# 130805_AriloRX_0_0.net
KiCad netlist of a schematic drawn in EAGLE
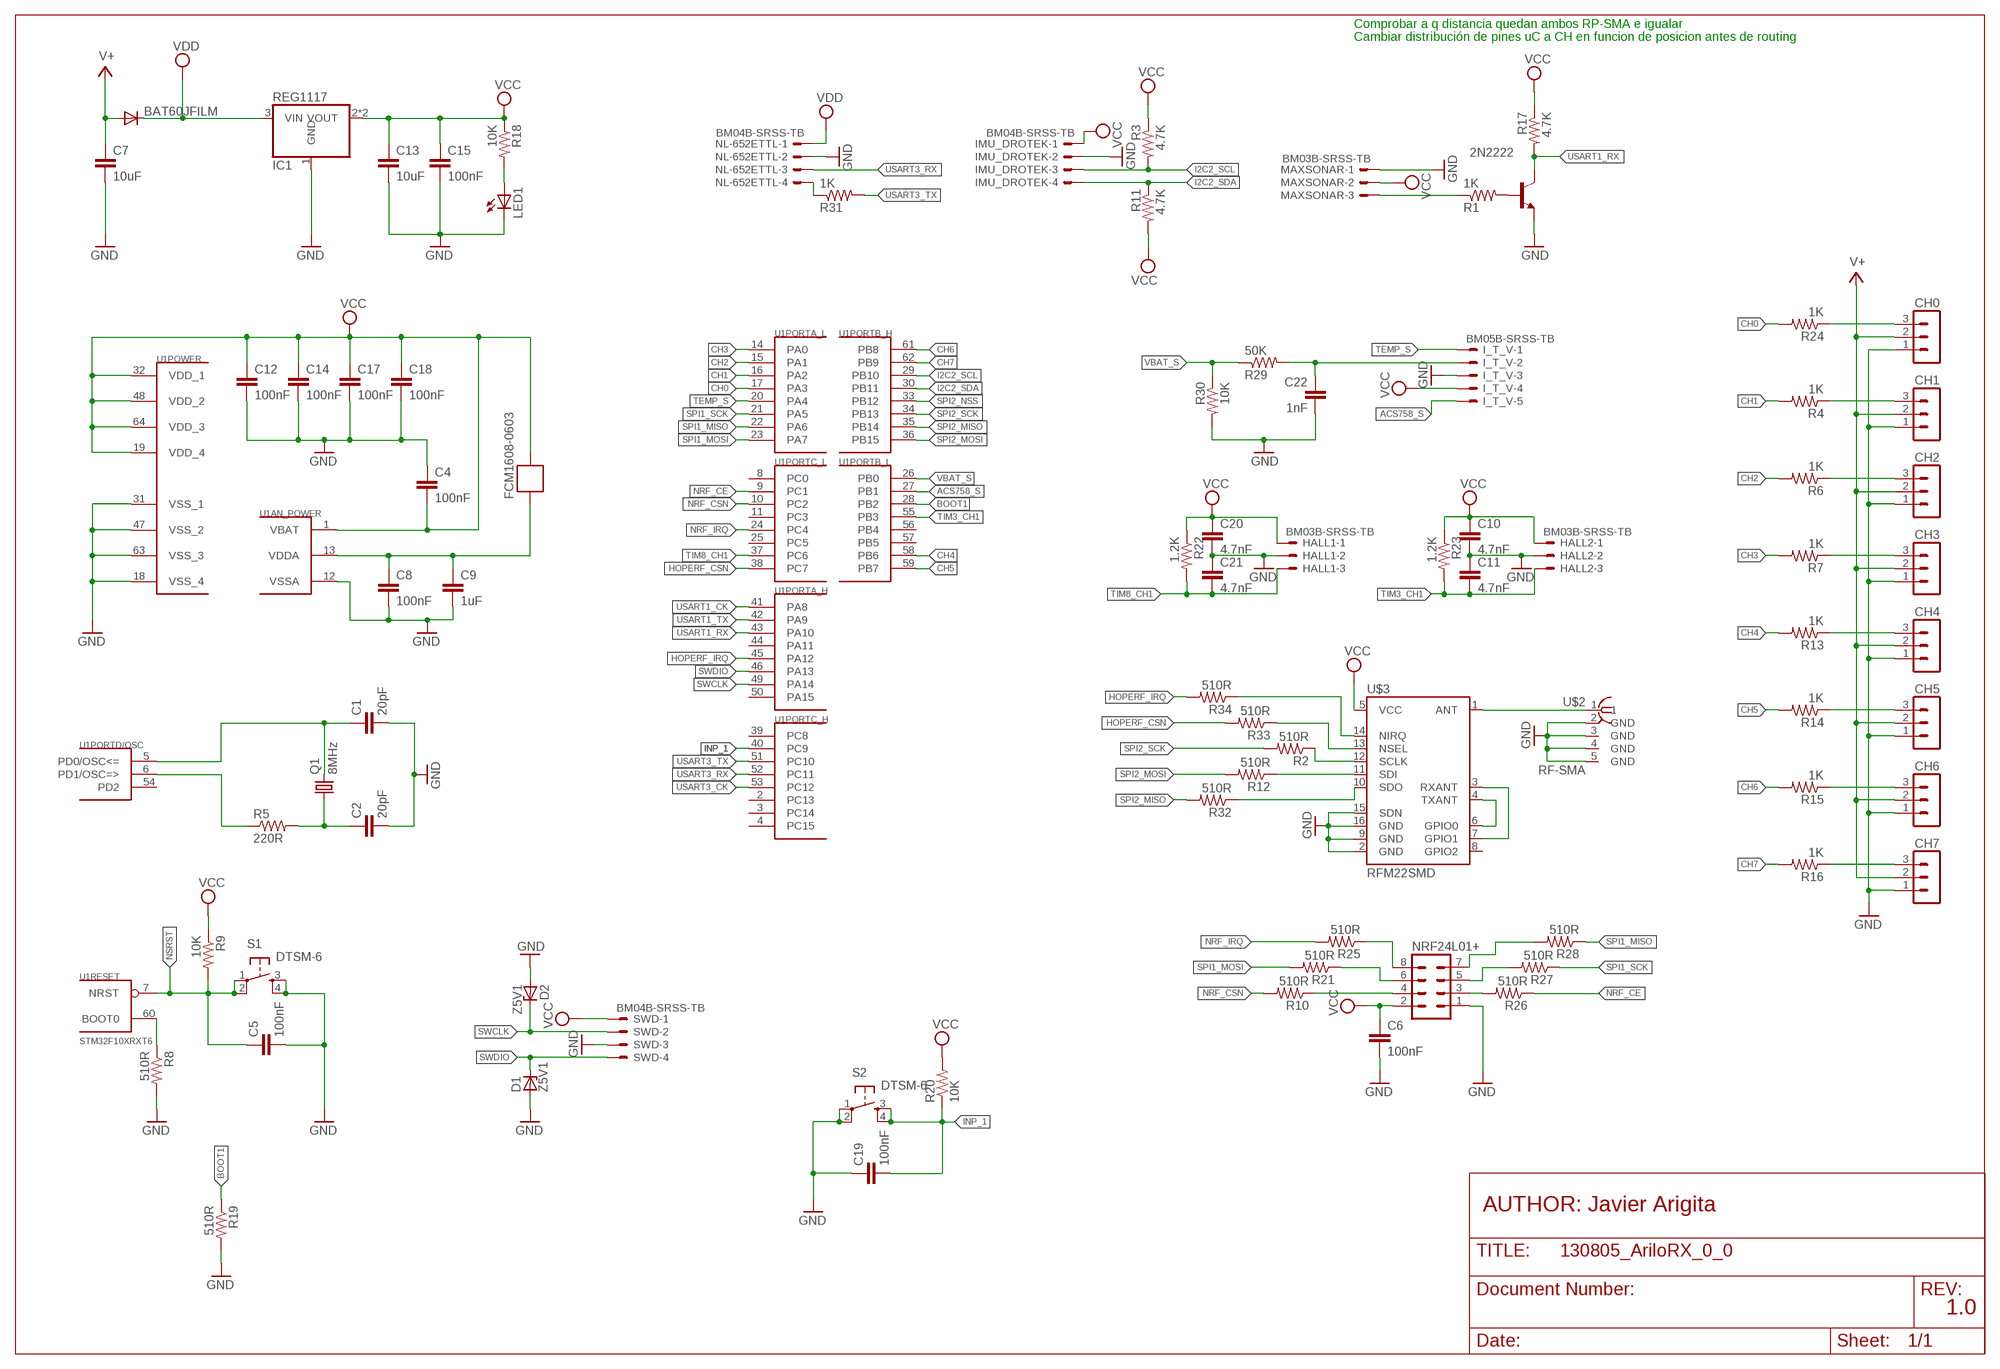
[diagram p0: schematic, sheet 1]

(export (version "E")
  (design (tool "Eeschema 10.0.6"))
  (components
    (comp (ref "2N2222")
      (value "MMBT2222ALT1-NPN-SOT23-BEC")
      (footprint "eagle-import:SOT23-BEC")
      (libsource (lib "eagle-import") (part "-NPN-SOT23-BECMMBT2222ALT1"))
    )
    (comp (ref "BAT60JFILM")
      (value "DIODE-SOD323-R")
      (footprint "eagle-import:SOD323-R")
      (libsource (lib "eagle-import") (part "DIODE-SOD323-R"))
    )
    (comp (ref "C1")
      (value "20pF")
      (footprint "eagle-import:C0805")
      (libsource (lib "eagle-import") (part "C-EUC0805"))
    )
    (comp (ref "C2")
      (value "20pF")
      (footprint "eagle-import:C0805")
      (libsource (lib "eagle-import") (part "C-EUC0805"))
    )
    (comp (ref "C4")
      (value "100nF")
      (footprint "eagle-import:C0805")
      (libsource (lib "eagle-import") (part "C-EUC0805"))
    )
    (comp (ref "C5")
      (value "100nF")
      (footprint "eagle-import:C0805")
      (libsource (lib "eagle-import") (part "C-EUC0805"))
    )
    (comp (ref "C6")
      (value "100nF")
      (footprint "eagle-import:C0805")
      (libsource (lib "eagle-import") (part "C-EUC0805"))
    )
    (comp (ref "C7")
      (value "10uF")
      (footprint "eagle-import:C3216")
      (libsource (lib "eagle-import") (part "resistor_C-EUC3216"))
    )
    (comp (ref "C8")
      (value "100nF")
      (footprint "eagle-import:C0805")
      (libsource (lib "eagle-import") (part "C-EUC0805"))
    )
    (comp (ref "C9")
      (value "1uF")
      (footprint "eagle-import:C3216")
      (libsource (lib "eagle-import") (part "resistor_C-EUC3216"))
    )
    (comp (ref "C10")
      (value "4.7nF")
      (footprint "eagle-import:C0805")
      (libsource (lib "eagle-import") (part "C-EUC0805"))
    )
    (comp (ref "C11")
      (value "4.7nF")
      (footprint "eagle-import:C0805")
      (libsource (lib "eagle-import") (part "C-EUC0805"))
    )
    (comp (ref "C12")
      (value "100nF")
      (footprint "eagle-import:C0805")
      (libsource (lib "eagle-import") (part "C-EUC0805"))
    )
    (comp (ref "C13")
      (value "10uF")
      (footprint "eagle-import:C3216")
      (libsource (lib "eagle-import") (part "resistor_C-EUC3216"))
    )
    (comp (ref "C14")
      (value "100nF")
      (footprint "eagle-import:C0805")
      (libsource (lib "eagle-import") (part "C-EUC0805"))
    )
    (comp (ref "C15")
      (value "100nF")
      (footprint "eagle-import:C0805")
      (libsource (lib "eagle-import") (part "C-EUC0805"))
    )
    (comp (ref "C17")
      (value "100nF")
      (footprint "eagle-import:C0805")
      (libsource (lib "eagle-import") (part "C-EUC0805"))
    )
    (comp (ref "C18")
      (value "100nF")
      (footprint "eagle-import:C0805")
      (libsource (lib "eagle-import") (part "C-EUC0805"))
    )
    (comp (ref "C19")
      (value "100nF")
      (footprint "eagle-import:C0805")
      (libsource (lib "eagle-import") (part "C-EUC0805"))
    )
    (comp (ref "C20")
      (value "4.7nF")
      (footprint "eagle-import:C0805")
      (libsource (lib "eagle-import") (part "C-EUC0805"))
    )
    (comp (ref "C21")
      (value "4.7nF")
      (footprint "eagle-import:C0805")
      (libsource (lib "eagle-import") (part "C-EUC0805"))
    )
    (comp (ref "C22")
      (value "1nF")
      (footprint "eagle-import:C0805")
      (libsource (lib "eagle-import") (part "C-EUC0805"))
    )
    (comp (ref "CH0")
      (value "MA03-1")
      (footprint "eagle-import:MA03-1")
      (libsource (lib "eagle-import") (part "MA03-1"))
    )
    (comp (ref "CH1")
      (value "MA03-1")
      (footprint "eagle-import:MA03-1")
      (libsource (lib "eagle-import") (part "MA03-1"))
    )
    (comp (ref "CH2")
      (value "MA03-1")
      (footprint "eagle-import:MA03-1")
      (libsource (lib "eagle-import") (part "MA03-1"))
    )
    (comp (ref "CH3")
      (value "MA03-1")
      (footprint "eagle-import:MA03-1")
      (libsource (lib "eagle-import") (part "MA03-1"))
    )
    (comp (ref "CH4")
      (value "MA03-1")
      (footprint "eagle-import:MA03-1")
      (libsource (lib "eagle-import") (part "MA03-1"))
    )
    (comp (ref "CH5")
      (value "MA03-1")
      (footprint "eagle-import:MA03-1")
      (libsource (lib "eagle-import") (part "MA03-1"))
    )
    (comp (ref "CH6")
      (value "MA03-1")
      (footprint "eagle-import:MA03-1")
      (libsource (lib "eagle-import") (part "MA03-1"))
    )
    (comp (ref "CH7")
      (value "MA03-1")
      (footprint "eagle-import:MA03-1")
      (libsource (lib "eagle-import") (part "MA03-1"))
    )
    (comp (ref "D1")
      (value "Z5V1")
      (footprint "eagle-import:SOD80C")
      (libsource (lib "eagle-import") (part "ZENER-DIODESOD80C"))
    )
    (comp (ref "D2")
      (value "Z5V1")
      (footprint "eagle-import:SOD80C")
      (libsource (lib "eagle-import") (part "ZENER-DIODESOD80C"))
    )
    (comp (ref "FCM1608-0603")
      (value "FERRITE-BEAD")
      (footprint "eagle-import:R0603")
      (libsource (lib "eagle-import") (part "FERRITE-BEAD"))
    )
    (comp (ref "HALL1")
      (value "BM03B-SRSS-TB")
      (footprint "eagle-import:BM03B-SRSS-TB")
      (libsource (lib "eagle-import") (part "?M03B-SRSS-TBB"))
    )
    (comp (ref "HALL2")
      (value "BM03B-SRSS-TB")
      (footprint "eagle-import:BM03B-SRSS-TB")
      (libsource (lib "eagle-import") (part "?M03B-SRSS-TBB"))
    )
    (comp (ref "IC1")
      (value "REG1117")
      (footprint "eagle-import:SOT223")
      (libsource (lib "eagle-import") (part "REG1117"))
    )
    (comp (ref "IMU_DROTEK")
      (value "BM04B-SRSS-TB")
      (footprint "eagle-import:BM04B-SRSS-TB")
      (libsource (lib "eagle-import") (part "?M04B-SRSS-TBB"))
    )
    (comp (ref "I_T_V")
      (value "BM05B-SRSS-TB")
      (footprint "eagle-import:BM05B-SRSS-TB")
      (libsource (lib "eagle-import") (part "?M05B-SRSS-TBB"))
    )
    (comp (ref "LED1")
      (value "LED0805")
      (footprint "eagle-import:CHIPLED_0805")
      (libsource (lib "eagle-import") (part "LED0805"))
    )
    (comp (ref "MAXSONAR")
      (value "BM03B-SRSS-TB")
      (footprint "eagle-import:BM03B-SRSS-TB")
      (libsource (lib "eagle-import") (part "?M03B-SRSS-TBB"))
    )
    (comp (ref "NL-652ETTL")
      (value "BM04B-SRSS-TB")
      (footprint "eagle-import:BM04B-SRSS-TB")
      (libsource (lib "eagle-import") (part "?M04B-SRSS-TBB"))
    )
    (comp (ref "NRF24L01+")
      (value "MA04-2")
      (footprint "eagle-import:MA04-2")
      (libsource (lib "eagle-import") (part "MA04-2"))
    )
    (comp (ref "Q1")
      (value "8MHz")
      (footprint "eagle-import:SM49")
      (libsource (lib "eagle-import") (part "CRYSTALSM49"))
    )
    (comp (ref "R1")
      (value "1K")
      (footprint "eagle-import:R0805")
      (libsource (lib "eagle-import") (part "RESISTOR0805"))
    )
    (comp (ref "R2")
      (value "510R")
      (footprint "eagle-import:R0805")
      (libsource (lib "eagle-import") (part "RESISTOR0805"))
    )
    (comp (ref "R3")
      (value "4.7K")
      (footprint "eagle-import:R0805")
      (libsource (lib "eagle-import") (part "RESISTOR0805"))
    )
    (comp (ref "R4")
      (value "1K")
      (footprint "eagle-import:R0805")
      (libsource (lib "eagle-import") (part "RESISTOR0805"))
    )
    (comp (ref "R5")
      (value "220R")
      (footprint "eagle-import:R0805")
      (libsource (lib "eagle-import") (part "RESISTOR0805"))
    )
    (comp (ref "R6")
      (value "1K")
      (footprint "eagle-import:R0805")
      (libsource (lib "eagle-import") (part "RESISTOR0805"))
    )
    (comp (ref "R7")
      (value "1K")
      (footprint "eagle-import:R0805")
      (libsource (lib "eagle-import") (part "RESISTOR0805"))
    )
    (comp (ref "R8")
      (value "510R")
      (footprint "eagle-import:R0805")
      (libsource (lib "eagle-import") (part "RESISTOR0805"))
    )
    (comp (ref "R9")
      (value "10K")
      (footprint "eagle-import:R0805")
      (libsource (lib "eagle-import") (part "RESISTOR0805"))
    )
    (comp (ref "R10")
      (value "510R")
      (footprint "eagle-import:R0805")
      (libsource (lib "eagle-import") (part "RESISTOR0805"))
    )
    (comp (ref "R11")
      (value "4.7K")
      (footprint "eagle-import:R0805")
      (libsource (lib "eagle-import") (part "RESISTOR0805"))
    )
    (comp (ref "R12")
      (value "510R")
      (footprint "eagle-import:R0805")
      (libsource (lib "eagle-import") (part "RESISTOR0805"))
    )
    (comp (ref "R13")
      (value "1K")
      (footprint "eagle-import:R0805")
      (libsource (lib "eagle-import") (part "RESISTOR0805"))
    )
    (comp (ref "R14")
      (value "1K")
      (footprint "eagle-import:R0805")
      (libsource (lib "eagle-import") (part "RESISTOR0805"))
    )
    (comp (ref "R15")
      (value "1K")
      (footprint "eagle-import:R0805")
      (libsource (lib "eagle-import") (part "RESISTOR0805"))
    )
    (comp (ref "R16")
      (value "1K")
      (footprint "eagle-import:R0805")
      (libsource (lib "eagle-import") (part "RESISTOR0805"))
    )
    (comp (ref "R17")
      (value "4.7K")
      (footprint "eagle-import:R0805")
      (libsource (lib "eagle-import") (part "RESISTOR0805"))
    )
    (comp (ref "R18")
      (value "10K")
      (footprint "eagle-import:R0805")
      (libsource (lib "eagle-import") (part "RESISTOR0805"))
    )
    (comp (ref "R19")
      (value "510R")
      (footprint "eagle-import:R0805")
      (libsource (lib "eagle-import") (part "RESISTOR0805"))
    )
    (comp (ref "R20")
      (value "10K")
      (footprint "eagle-import:R0805")
      (libsource (lib "eagle-import") (part "RESISTOR0805"))
    )
    (comp (ref "R21")
      (value "510R")
      (footprint "eagle-import:R0805")
      (libsource (lib "eagle-import") (part "RESISTOR0805"))
    )
    (comp (ref "R22")
      (value "1.2K")
      (footprint "eagle-import:R0805")
      (libsource (lib "eagle-import") (part "RESISTOR0805"))
    )
    (comp (ref "R23")
      (value "1.2K")
      (footprint "eagle-import:R0805")
      (libsource (lib "eagle-import") (part "RESISTOR0805"))
    )
    (comp (ref "R24")
      (value "1K")
      (footprint "eagle-import:R0805")
      (libsource (lib "eagle-import") (part "RESISTOR0805"))
    )
    (comp (ref "R25")
      (value "510R")
      (footprint "eagle-import:R0805")
      (libsource (lib "eagle-import") (part "RESISTOR0805"))
    )
    (comp (ref "R26")
      (value "510R")
      (footprint "eagle-import:R0805")
      (libsource (lib "eagle-import") (part "RESISTOR0805"))
    )
    (comp (ref "R27")
      (value "510R")
      (footprint "eagle-import:R0805")
      (libsource (lib "eagle-import") (part "RESISTOR0805"))
    )
    (comp (ref "R28")
      (value "510R")
      (footprint "eagle-import:R0805")
      (libsource (lib "eagle-import") (part "RESISTOR0805"))
    )
    (comp (ref "R29")
      (value "50K")
      (footprint "eagle-import:R0805")
      (libsource (lib "eagle-import") (part "RESISTOR0805"))
    )
    (comp (ref "R30")
      (value "10K")
      (footprint "eagle-import:R0805")
      (libsource (lib "eagle-import") (part "RESISTOR0805"))
    )
    (comp (ref "R31")
      (value "1K")
      (footprint "eagle-import:R0805")
      (libsource (lib "eagle-import") (part "RESISTOR0805"))
    )
    (comp (ref "R32")
      (value "510R")
      (footprint "eagle-import:R0805")
      (libsource (lib "eagle-import") (part "RESISTOR0805"))
    )
    (comp (ref "R33")
      (value "510R")
      (footprint "eagle-import:R0805")
      (libsource (lib "eagle-import") (part "RESISTOR0805"))
    )
    (comp (ref "R34")
      (value "510R")
      (footprint "eagle-import:R0805")
      (libsource (lib "eagle-import") (part "RESISTOR0805"))
    )
    (comp (ref "S1")
      (value "DTSM-6")
      (footprint "eagle-import:DTSM-6")
      (libsource (lib "eagle-import") (part "DTSM-6"))
    )
    (comp (ref "S2")
      (value "DTSM-6")
      (footprint "eagle-import:DTSM-6")
      (libsource (lib "eagle-import") (part "DTSM-6"))
    )
    (comp (ref "SWD")
      (value "BM04B-SRSS-TB")
      (footprint "eagle-import:BM04B-SRSS-TB")
      (libsource (lib "eagle-import") (part "?M04B-SRSS-TBB"))
    )
    (comp (ref "U$2")
      (value "RF-SMA")
      (footprint "eagle-import:BU-SMA-H")
      (libsource (lib "eagle-import") (part "RF-SMA"))
    )
    (comp (ref "U$3")
      (value "RFM22SMD")
      (footprint "eagle-import:RFM22-XXX-S2")
      (libsource (lib "eagle-import") (part "RFM22SMD"))
    )
    (comp (ref "U1")
      (value "STM32F10XRXT6")
      (footprint "eagle-import:TQFP64")
      (libsource (lib "eagle-import") (part "STM32F10XRXT6"))
    )
  )
  (nets
    (net (code "1") (name "ACS758_S") (class "Default")
      (node (ref "I_T_V") (pin "5") (pinfunction "S_5") (pintype "passive"))
      (node (ref "U1") (pin "27") (pinfunction "PB1_27") (pintype "bidirectional"))
    )
    (net (code "2") (name "BOOT1") (class "Default")
      (node (ref "R19") (pin "1") (pinfunction "1_1") (pintype "passive"))
      (node (ref "U1") (pin "28") (pinfunction "PB2_28") (pintype "bidirectional"))
    )
    (net (code "3") (name "CH0") (class "Default")
      (node (ref "R24") (pin "2") (pinfunction "2_2") (pintype "passive"))
      (node (ref "U1") (pin "17") (pinfunction "PA3_17") (pintype "bidirectional"))
    )
    (net (code "4") (name "CH1") (class "Default")
      (node (ref "R4") (pin "2") (pinfunction "2_2") (pintype "passive"))
      (node (ref "U1") (pin "16") (pinfunction "PA2_16") (pintype "bidirectional"))
    )
    (net (code "5") (name "CH2") (class "Default")
      (node (ref "R6") (pin "2") (pinfunction "2_2") (pintype "passive"))
      (node (ref "U1") (pin "15") (pinfunction "PA1_15") (pintype "bidirectional"))
    )
    (net (code "6") (name "CH3") (class "Default")
      (node (ref "R7") (pin "2") (pinfunction "2_2") (pintype "passive"))
      (node (ref "U1") (pin "14") (pinfunction "PA0_14") (pintype "bidirectional"))
    )
    (net (code "7") (name "CH4") (class "Default")
      (node (ref "R13") (pin "2") (pinfunction "2_2") (pintype "passive"))
      (node (ref "U1") (pin "58") (pinfunction "PB6_58") (pintype "bidirectional"))
    )
    (net (code "8") (name "CH5") (class "Default")
      (node (ref "R14") (pin "2") (pinfunction "2_2") (pintype "passive"))
      (node (ref "U1") (pin "59") (pinfunction "PB7_59") (pintype "bidirectional"))
    )
    (net (code "9") (name "CH6") (class "Default")
      (node (ref "R15") (pin "2") (pinfunction "2_2") (pintype "passive"))
      (node (ref "U1") (pin "61") (pinfunction "PB8_61") (pintype "bidirectional"))
    )
    (net (code "10") (name "CH7") (class "Default")
      (node (ref "R16") (pin "2") (pinfunction "2_2") (pintype "passive"))
      (node (ref "U1") (pin "62") (pinfunction "PB9_62") (pintype "bidirectional"))
    )
    (net (code "11") (name "GND") (class "Default")
      (node (ref "2N2222") (pin "E") (pinfunction "E_E") (pintype "passive"))
      (node (ref "C1") (pin "2") (pinfunction "2_2") (pintype "passive"))
      (node (ref "C10") (pin "2") (pinfunction "2_2") (pintype "passive"))
      (node (ref "C11") (pin "1") (pinfunction "1_1") (pintype "passive"))
      (node (ref "C12") (pin "2") (pinfunction "2_2") (pintype "passive"))
      (node (ref "C13") (pin "2") (pinfunction "2_2") (pintype "passive"))
      (node (ref "C14") (pin "2") (pinfunction "2_2") (pintype "passive"))
      (node (ref "C15") (pin "2") (pinfunction "2_2") (pintype "passive"))
      (node (ref "C17") (pin "2") (pinfunction "2_2") (pintype "passive"))
      (node (ref "C18") (pin "2") (pinfunction "2_2") (pintype "passive"))
      (node (ref "C19") (pin "1") (pinfunction "1_1") (pintype "passive"))
      (node (ref "C2") (pin "2") (pinfunction "2_2") (pintype "passive"))
      (node (ref "C20") (pin "2") (pinfunction "2_2") (pintype "passive"))
      (node (ref "C21") (pin "1") (pinfunction "1_1") (pintype "passive"))
      (node (ref "C22") (pin "2") (pinfunction "2_2") (pintype "passive"))
      (node (ref "C4") (pin "1") (pinfunction "1_1") (pintype "passive"))
      (node (ref "C5") (pin "2") (pinfunction "2_2") (pintype "passive"))
      (node (ref "C6") (pin "2") (pinfunction "2_2") (pintype "passive"))
      (node (ref "C7") (pin "2") (pinfunction "2_2") (pintype "passive"))
      (node (ref "C8") (pin "2") (pinfunction "2_2") (pintype "passive"))
      (node (ref "C9") (pin "2") (pinfunction "2_2") (pintype "passive"))
      (node (ref "CH0") (pin "1") (pinfunction "1_1") (pintype "passive"))
      (node (ref "CH1") (pin "1") (pinfunction "1_1") (pintype "passive"))
      (node (ref "CH2") (pin "1") (pinfunction "1_1") (pintype "passive"))
      (node (ref "CH3") (pin "1") (pinfunction "1_1") (pintype "passive"))
      (node (ref "CH4") (pin "1") (pinfunction "1_1") (pintype "passive"))
      (node (ref "CH5") (pin "1") (pinfunction "1_1") (pintype "passive"))
      (node (ref "CH6") (pin "1") (pinfunction "1_1") (pintype "passive"))
      (node (ref "CH7") (pin "1") (pinfunction "1_1") (pintype "passive"))
      (node (ref "D1") (pin "A") (pinfunction "A_A") (pintype "passive"))
      (node (ref "D2") (pin "A") (pinfunction "A_A") (pintype "passive"))
      (node (ref "HALL1") (pin "2") (pinfunction "S_2") (pintype "passive"))
      (node (ref "HALL2") (pin "2") (pinfunction "S_2") (pintype "passive"))
      (node (ref "IC1") (pin "1") (pinfunction "GND_1") (pintype "power_in"))
      (node (ref "IMU_DROTEK") (pin "2") (pinfunction "S_2") (pintype "passive"))
      (node (ref "I_T_V") (pin "3") (pinfunction "S_3") (pintype "passive"))
      (node (ref "LED1") (pin "C") (pinfunction "C_C") (pintype "passive"))
      (node (ref "MAXSONAR") (pin "1") (pinfunction "S_1") (pintype "passive"))
      (node (ref "NL-652ETTL") (pin "2") (pinfunction "S_2") (pintype "passive"))
      (node (ref "NRF24L01+") (pin "1") (pinfunction "1_1") (pintype "passive"))
      (node (ref "R19") (pin "2") (pinfunction "2_2") (pintype "passive"))
      (node (ref "R30") (pin "2") (pinfunction "2_2") (pintype "passive"))
      (node (ref "R8") (pin "2") (pinfunction "2_2") (pintype "passive"))
      (node (ref "S1") (pin "3") (pinfunction "3_3") (pintype "passive"))
      (node (ref "S1") (pin "4") (pinfunction "4_4") (pintype "passive"))
      (node (ref "S2") (pin "1") (pinfunction "1_1") (pintype "passive"))
      (node (ref "S2") (pin "2") (pinfunction "2_2") (pintype "passive"))
      (node (ref "SWD") (pin "3") (pinfunction "S_3") (pintype "passive"))
      (node (ref "U$2") (pin "2") (pinfunction "GND_2") (pintype "power_in"))
      (node (ref "U$2") (pin "3") (pinfunction "GND_3") (pintype "bidirectional"))
      (node (ref "U$2") (pin "4") (pinfunction "GND_4") (pintype "bidirectional"))
      (node (ref "U$2") (pin "5") (pinfunction "GND_5") (pintype "bidirectional"))
      (node (ref "U$3") (pin "15") (pinfunction "SDN_15") (pintype "input"))
      (node (ref "U$3") (pin "16") (pinfunction "GND_16") (pintype "power_in"))
      (node (ref "U$3") (pin "2") (pinfunction "GND_2") (pintype "power_in"))
      (node (ref "U$3") (pin "9") (pinfunction "GND_9") (pintype "power_in"))
      (node (ref "U1") (pin "12") (pinfunction "VSSA_12") (pintype "power_in"))
      (node (ref "U1") (pin "18") (pinfunction "VSS_4_18") (pintype "power_in"))
      (node (ref "U1") (pin "31") (pinfunction "VSS_1_31") (pintype "power_in"))
      (node (ref "U1") (pin "47") (pinfunction "VSS_2_47") (pintype "power_in"))
      (node (ref "U1") (pin "63") (pinfunction "VSS_3_63") (pintype "power_in"))
    )
    (net (code "12") (name "HOPERF_CSN") (class "Default")
      (node (ref "R33") (pin "2") (pinfunction "2_2") (pintype "passive"))
      (node (ref "U1") (pin "38") (pinfunction "PC7_38") (pintype "bidirectional"))
    )
    (net (code "13") (name "HOPERF_IRQ") (class "Default")
      (node (ref "R34") (pin "2") (pinfunction "2_2") (pintype "passive"))
      (node (ref "U1") (pin "45") (pinfunction "PA12_45") (pintype "bidirectional"))
    )
    (net (code "14") (name "I2C2_SCL") (class "Default")
      (node (ref "IMU_DROTEK") (pin "3") (pinfunction "S_3") (pintype "passive"))
      (node (ref "R3") (pin "2") (pinfunction "2_2") (pintype "passive"))
      (node (ref "U1") (pin "29") (pinfunction "PB10_29") (pintype "bidirectional"))
    )
    (net (code "15") (name "I2C2_SDA") (class "Default")
      (node (ref "IMU_DROTEK") (pin "4") (pinfunction "S_4") (pintype "passive"))
      (node (ref "R11") (pin "1") (pinfunction "1_1") (pintype "passive"))
      (node (ref "U1") (pin "30") (pinfunction "PB11_30") (pintype "bidirectional"))
    )
    (net (code "16") (name "INP_1") (class "Default")
      (node (ref "C19") (pin "2") (pinfunction "2_2") (pintype "passive"))
      (node (ref "R20") (pin "1") (pinfunction "1_1") (pintype "passive"))
      (node (ref "S2") (pin "3") (pinfunction "3_3") (pintype "passive"))
      (node (ref "S2") (pin "4") (pinfunction "4_4") (pintype "passive"))
      (node (ref "U1") (pin "40") (pinfunction "PC9_40") (pintype "bidirectional"))
    )
    (net (code "17") (name "NRF_CE") (class "Default")
      (node (ref "R26") (pin "1") (pinfunction "1_1") (pintype "passive"))
      (node (ref "U1") (pin "9") (pinfunction "PC1_9") (pintype "bidirectional"))
    )
    (net (code "18") (name "NRF_CSN") (class "Default")
      (node (ref "R10") (pin "2") (pinfunction "2_2") (pintype "passive"))
      (node (ref "U1") (pin "10") (pinfunction "PC2_10") (pintype "bidirectional"))
    )
    (net (code "19") (name "NRF_IRQ") (class "Default")
      (node (ref "R25") (pin "2") (pinfunction "2_2") (pintype "passive"))
      (node (ref "U1") (pin "24") (pinfunction "PC4_24") (pintype "bidirectional"))
    )
    (net (code "20") (name "NSRST") (class "Default")
      (node (ref "C5") (pin "1") (pinfunction "1_1") (pintype "passive"))
      (node (ref "R9") (pin "2") (pinfunction "2_2") (pintype "passive"))
      (node (ref "S1") (pin "1") (pinfunction "1_1") (pintype "passive"))
      (node (ref "S1") (pin "2") (pinfunction "2_2") (pintype "passive"))
      (node (ref "U1") (pin "7") (pinfunction "NRST_7") (pintype "input"))
    )
    (net (code "21") (name "Net-(2N2222-PadB)") (class "Default")
      (node (ref "2N2222") (pin "B") (pinfunction "B_B") (pintype "passive"))
      (node (ref "R1") (pin "2") (pinfunction "2_2") (pintype "passive"))
    )
    (net (code "22") (name "Net-(C2-Pad1)") (class "Default")
      (node (ref "C2") (pin "1") (pinfunction "1_1") (pintype "passive"))
      (node (ref "Q1") (pin "1") (pinfunction "1_1") (pintype "passive"))
      (node (ref "R5") (pin "2") (pinfunction "2_2") (pintype "passive"))
    )
    (net (code "23") (name "Net-(CH0-Pad3)") (class "Default")
      (node (ref "CH0") (pin "3") (pinfunction "3_3") (pintype "passive"))
      (node (ref "R24") (pin "1") (pinfunction "1_1") (pintype "passive"))
    )
    (net (code "24") (name "Net-(CH1-Pad3)") (class "Default")
      (node (ref "CH1") (pin "3") (pinfunction "3_3") (pintype "passive"))
      (node (ref "R4") (pin "1") (pinfunction "1_1") (pintype "passive"))
    )
    (net (code "25") (name "Net-(CH2-Pad3)") (class "Default")
      (node (ref "CH2") (pin "3") (pinfunction "3_3") (pintype "passive"))
      (node (ref "R6") (pin "1") (pinfunction "1_1") (pintype "passive"))
    )
    (net (code "26") (name "Net-(CH3-Pad3)") (class "Default")
      (node (ref "CH3") (pin "3") (pinfunction "3_3") (pintype "passive"))
      (node (ref "R7") (pin "1") (pinfunction "1_1") (pintype "passive"))
    )
    (net (code "27") (name "Net-(CH4-Pad3)") (class "Default")
      (node (ref "CH4") (pin "3") (pinfunction "3_3") (pintype "passive"))
      (node (ref "R13") (pin "1") (pinfunction "1_1") (pintype "passive"))
    )
    (net (code "28") (name "Net-(CH5-Pad3)") (class "Default")
      (node (ref "CH5") (pin "3") (pinfunction "3_3") (pintype "passive"))
      (node (ref "R14") (pin "1") (pinfunction "1_1") (pintype "passive"))
    )
    (net (code "29") (name "Net-(CH6-Pad3)") (class "Default")
      (node (ref "CH6") (pin "3") (pinfunction "3_3") (pintype "passive"))
      (node (ref "R15") (pin "1") (pinfunction "1_1") (pintype "passive"))
    )
    (net (code "30") (name "Net-(CH7-Pad3)") (class "Default")
      (node (ref "CH7") (pin "3") (pinfunction "3_3") (pintype "passive"))
      (node (ref "R16") (pin "1") (pinfunction "1_1") (pintype "passive"))
    )
    (net (code "31") (name "Net-(FCM1608-0603-P$2)") (class "Default")
      (node (ref "C8") (pin "1") (pinfunction "1_1") (pintype "passive"))
      (node (ref "C9") (pin "1") (pinfunction "1_1") (pintype "passive"))
      (node (ref "FCM1608-0603") (pin "2") (pinfunction "P$2_2") (pintype "bidirectional"))
      (node (ref "U1") (pin "13") (pinfunction "VDDA_13") (pintype "power_in"))
    )
    (net (code "32") (name "Net-(I_T_VB-S)") (class "Default")
      (node (ref "C22") (pin "1") (pinfunction "1_1") (pintype "passive"))
      (node (ref "I_T_V") (pin "2") (pinfunction "S_2") (pintype "passive"))
      (node (ref "R29") (pin "2") (pinfunction "2_2") (pintype "passive"))
    )
    (net (code "33") (name "Net-(LED1-PadA)") (class "Default")
      (node (ref "LED1") (pin "A") (pinfunction "A_A") (pintype "passive"))
      (node (ref "R18") (pin "2") (pinfunction "2_2") (pintype "passive"))
    )
    (net (code "34") (name "Net-(MAXSONARC-S)") (class "Default")
      (node (ref "MAXSONAR") (pin "3") (pinfunction "S_3") (pintype "passive"))
      (node (ref "R1") (pin "1") (pinfunction "1_1") (pintype "passive"))
    )
    (net (code "35") (name "Net-(NL-652ETTLD-S)") (class "Default")
      (node (ref "NL-652ETTL") (pin "4") (pinfunction "S_4") (pintype "passive"))
      (node (ref "R31") (pin "1") (pinfunction "1_1") (pintype "passive"))
    )
    (net (code "36") (name "Net-(NRF24L01+-Pad3)") (class "Default")
      (node (ref "NRF24L01+") (pin "3") (pinfunction "3_3") (pintype "passive"))
      (node (ref "R26") (pin "2") (pinfunction "2_2") (pintype "passive"))
    )
    (net (code "37") (name "Net-(NRF24L01+-Pad4)") (class "Default")
      (node (ref "NRF24L01+") (pin "4") (pinfunction "4_4") (pintype "passive"))
      (node (ref "R10") (pin "1") (pinfunction "1_1") (pintype "passive"))
    )
    (net (code "38") (name "Net-(NRF24L01+-Pad5)") (class "Default")
      (node (ref "NRF24L01+") (pin "5") (pinfunction "5_5") (pintype "passive"))
      (node (ref "R27") (pin "2") (pinfunction "2_2") (pintype "passive"))
    )
    (net (code "39") (name "Net-(NRF24L01+-Pad6)") (class "Default")
      (node (ref "NRF24L01+") (pin "6") (pinfunction "6_6") (pintype "passive"))
      (node (ref "R21") (pin "1") (pinfunction "1_1") (pintype "passive"))
    )
    (net (code "40") (name "Net-(NRF24L01+-Pad7)") (class "Default")
      (node (ref "NRF24L01+") (pin "7") (pinfunction "7_7") (pintype "passive"))
      (node (ref "R28") (pin "2") (pinfunction "2_2") (pintype "passive"))
    )
    (net (code "41") (name "Net-(NRF24L01+-Pad8)") (class "Default")
      (node (ref "NRF24L01+") (pin "8") (pinfunction "8_8") (pintype "passive"))
      (node (ref "R25") (pin "1") (pinfunction "1_1") (pintype "passive"))
    )
    (net (code "42") (name "Net-(U$3-ANT)") (class "Default")
      (node (ref "U$2") (pin "1") (pinfunction "1_1") (pintype "passive"))
      (node (ref "U$3") (pin "1") (pinfunction "ANT_1") (pintype "bidirectional"))
    )
    (net (code "43") (name "Net-(U$3-GPIO0)") (class "Default")
      (node (ref "U$3") (pin "4") (pinfunction "TXANT_4") (pintype "input"))
      (node (ref "U$3") (pin "6") (pinfunction "GPIO0_6") (pintype "bidirectional"))
    )
    (net (code "44") (name "Net-(U$3-GPIO1)") (class "Default")
      (node (ref "U$3") (pin "3") (pinfunction "RXANT_3") (pintype "input"))
      (node (ref "U$3") (pin "7") (pinfunction "GPIO1_7") (pintype "bidirectional"))
    )
    (net (code "45") (name "Net-(U$3-NIRQ)") (class "Default")
      (node (ref "R34") (pin "1") (pinfunction "1_1") (pintype "passive"))
      (node (ref "U$3") (pin "14") (pinfunction "NIRQ_14") (pintype "output"))
    )
    (net (code "46") (name "Net-(U$3-NSEL)") (class "Default")
      (node (ref "R33") (pin "1") (pinfunction "1_1") (pintype "passive"))
      (node (ref "U$3") (pin "13") (pinfunction "NSEL_13") (pintype "input"))
    )
    (net (code "47") (name "Net-(U$3-SCLK)") (class "Default")
      (node (ref "R2") (pin "1") (pinfunction "1_1") (pintype "passive"))
      (node (ref "U$3") (pin "12") (pinfunction "SCLK_12") (pintype "input"))
    )
    (net (code "48") (name "Net-(U$3-SDI)") (class "Default")
      (node (ref "R12") (pin "1") (pinfunction "1_1") (pintype "passive"))
      (node (ref "U$3") (pin "11") (pinfunction "SDI_11") (pintype "input"))
    )
    (net (code "49") (name "Net-(U$3-SDO)") (class "Default")
      (node (ref "R32") (pin "1") (pinfunction "1_1") (pintype "passive"))
      (node (ref "U$3") (pin "10") (pinfunction "SDO_10") (pintype "output"))
    )
    (net (code "50") (name "Net-(U1H-PD0{slash}OSC<=)") (class "Default")
      (node (ref "C1") (pin "1") (pinfunction "1_1") (pintype "passive"))
      (node (ref "Q1") (pin "2") (pinfunction "2_2") (pintype "passive"))
      (node (ref "U1") (pin "5") (pinfunction "PD0/OSC<=_5") (pintype "bidirectional"))
    )
    (net (code "51") (name "Net-(U1H-PD1{slash}OSC=>)") (class "Default")
      (node (ref "R5") (pin "1") (pinfunction "1_1") (pintype "passive"))
      (node (ref "U1") (pin "6") (pinfunction "PD1/OSC=>_6") (pintype "bidirectional"))
    )
    (net (code "52") (name "Net-(U1J-BOOT0)") (class "Default")
      (node (ref "R8") (pin "1") (pinfunction "1_1") (pintype "passive"))
      (node (ref "U1") (pin "60") (pinfunction "BOOT0_60") (pintype "input"))
    )
    (net (code "53") (name "SPI1_MISO") (class "Default")
      (node (ref "R28") (pin "1") (pinfunction "1_1") (pintype "passive"))
      (node (ref "U1") (pin "22") (pinfunction "PA6_22") (pintype "bidirectional"))
    )
    (net (code "54") (name "SPI1_MOSI") (class "Default")
      (node (ref "R21") (pin "2") (pinfunction "2_2") (pintype "passive"))
      (node (ref "U1") (pin "23") (pinfunction "PA7_23") (pintype "bidirectional"))
    )
    (net (code "55") (name "SPI1_SCK") (class "Default")
      (node (ref "R27") (pin "1") (pinfunction "1_1") (pintype "passive"))
      (node (ref "U1") (pin "21") (pinfunction "PA5_21") (pintype "bidirectional"))
    )
    (net (code "56") (name "SPI2_MISO") (class "Default")
      (node (ref "R32") (pin "2") (pinfunction "2_2") (pintype "passive"))
      (node (ref "U1") (pin "35") (pinfunction "PB14_35") (pintype "bidirectional"))
    )
    (net (code "57") (name "SPI2_MOSI") (class "Default")
      (node (ref "R12") (pin "2") (pinfunction "2_2") (pintype "passive"))
      (node (ref "U1") (pin "36") (pinfunction "PB15_36") (pintype "bidirectional"))
    )
    (net (code "58") (name "SPI2_NSS") (class "Default")
      (node (ref "U1") (pin "33") (pinfunction "PB12_33") (pintype "bidirectional"))
    )
    (net (code "59") (name "SPI2_SCK") (class "Default")
      (node (ref "R2") (pin "2") (pinfunction "2_2") (pintype "passive"))
      (node (ref "U1") (pin "34") (pinfunction "PB13_34") (pintype "bidirectional"))
    )
    (net (code "60") (name "SWCLK") (class "Default")
      (node (ref "D2") (pin "C") (pinfunction "C_C") (pintype "passive"))
      (node (ref "SWD") (pin "2") (pinfunction "S_2") (pintype "passive"))
      (node (ref "U1") (pin "49") (pinfunction "PA14_49") (pintype "bidirectional"))
    )
    (net (code "61") (name "SWDIO") (class "Default")
      (node (ref "D1") (pin "C") (pinfunction "C_C") (pintype "passive"))
      (node (ref "SWD") (pin "4") (pinfunction "S_4") (pintype "passive"))
      (node (ref "U1") (pin "46") (pinfunction "PA13_46") (pintype "bidirectional"))
    )
    (net (code "62") (name "TEMP_S") (class "Default")
      (node (ref "I_T_V") (pin "1") (pinfunction "S_1") (pintype "passive"))
      (node (ref "U1") (pin "20") (pinfunction "PA4_20") (pintype "bidirectional"))
    )
    (net (code "63") (name "TIM3_CH1") (class "Default")
      (node (ref "C11") (pin "2") (pinfunction "2_2") (pintype "passive"))
      (node (ref "HALL2") (pin "3") (pinfunction "S_3") (pintype "passive"))
      (node (ref "R23") (pin "2") (pinfunction "2_2") (pintype "passive"))
      (node (ref "U1") (pin "55") (pinfunction "PB3_55") (pintype "bidirectional"))
    )
    (net (code "64") (name "TIM8_CH1") (class "Default")
      (node (ref "C21") (pin "2") (pinfunction "2_2") (pintype "passive"))
      (node (ref "HALL1") (pin "3") (pinfunction "S_3") (pintype "passive"))
      (node (ref "R22") (pin "2") (pinfunction "2_2") (pintype "passive"))
      (node (ref "U1") (pin "37") (pinfunction "PC6_37") (pintype "bidirectional"))
    )
    (net (code "65") (name "USART1_CK") (class "Default")
      (node (ref "U1") (pin "41") (pinfunction "PA8_41") (pintype "bidirectional"))
    )
    (net (code "66") (name "USART1_RX") (class "Default")
      (node (ref "2N2222") (pin "C") (pinfunction "C_C") (pintype "passive"))
      (node (ref "R17") (pin "2") (pinfunction "2_2") (pintype "passive"))
      (node (ref "U1") (pin "43") (pinfunction "PA10_43") (pintype "bidirectional"))
    )
    (net (code "67") (name "USART1_TX") (class "Default")
      (node (ref "U1") (pin "42") (pinfunction "PA9_42") (pintype "bidirectional"))
    )
    (net (code "68") (name "USART3_CK") (class "Default")
      (node (ref "U1") (pin "53") (pinfunction "PC12_53") (pintype "bidirectional"))
    )
    (net (code "69") (name "USART3_RX") (class "Default")
      (node (ref "NL-652ETTL") (pin "3") (pinfunction "S_3") (pintype "passive"))
      (node (ref "U1") (pin "52") (pinfunction "PC11_52") (pintype "bidirectional"))
    )
    (net (code "70") (name "USART3_TX") (class "Default")
      (node (ref "R31") (pin "2") (pinfunction "2_2") (pintype "passive"))
      (node (ref "U1") (pin "51") (pinfunction "PC10_51") (pintype "bidirectional"))
    )
    (net (code "71") (name "V+") (class "Default")
      (node (ref "BAT60JFILM") (pin "A") (pinfunction "A_A") (pintype "passive"))
      (node (ref "C7") (pin "1") (pinfunction "1_1") (pintype "passive"))
      (node (ref "CH0") (pin "2") (pinfunction "2_2") (pintype "passive"))
      (node (ref "CH1") (pin "2") (pinfunction "2_2") (pintype "passive"))
      (node (ref "CH2") (pin "2") (pinfunction "2_2") (pintype "passive"))
      (node (ref "CH3") (pin "2") (pinfunction "2_2") (pintype "passive"))
      (node (ref "CH4") (pin "2") (pinfunction "2_2") (pintype "passive"))
      (node (ref "CH5") (pin "2") (pinfunction "2_2") (pintype "passive"))
      (node (ref "CH6") (pin "2") (pinfunction "2_2") (pintype "passive"))
      (node (ref "CH7") (pin "2") (pinfunction "2_2") (pintype "passive"))
    )
    (net (code "72") (name "VBAT_S") (class "Default")
      (node (ref "R29") (pin "1") (pinfunction "1_1") (pintype "passive"))
      (node (ref "R30") (pin "1") (pinfunction "1_1") (pintype "passive"))
      (node (ref "U1") (pin "26") (pinfunction "PB0_26") (pintype "bidirectional"))
    )
    (net (code "73") (name "VCC") (class "Default")
      (node (ref "C10") (pin "1") (pinfunction "1_1") (pintype "passive"))
      (node (ref "C12") (pin "1") (pinfunction "1_1") (pintype "passive"))
      (node (ref "C13") (pin "1") (pinfunction "1_1") (pintype "passive"))
      (node (ref "C14") (pin "1") (pinfunction "1_1") (pintype "passive"))
      (node (ref "C15") (pin "1") (pinfunction "1_1") (pintype "passive"))
      (node (ref "C17") (pin "1") (pinfunction "1_1") (pintype "passive"))
      (node (ref "C18") (pin "1") (pinfunction "1_1") (pintype "passive"))
      (node (ref "C20") (pin "1") (pinfunction "1_1") (pintype "passive"))
      (node (ref "C4") (pin "2") (pinfunction "2_2") (pintype "passive"))
      (node (ref "C6") (pin "1") (pinfunction "1_1") (pintype "passive"))
      (node (ref "FCM1608-0603") (pin "1") (pinfunction "P$1_1") (pintype "bidirectional"))
      (node (ref "HALL1") (pin "1") (pinfunction "S_1") (pintype "passive"))
      (node (ref "HALL2") (pin "1") (pinfunction "S_1") (pintype "passive"))
      (node (ref "IC1") (pin "2") (pinfunction "VOUT_2") (pintype "power_in"))
      (node (ref "IC1") (pin "4") (pinfunction "VOUT_4") (pintype "power_in"))
      (node (ref "IMU_DROTEK") (pin "1") (pinfunction "S_1") (pintype "passive"))
      (node (ref "I_T_V") (pin "4") (pinfunction "S_4") (pintype "passive"))
      (node (ref "MAXSONAR") (pin "2") (pinfunction "S_2") (pintype "passive"))
      (node (ref "NRF24L01+") (pin "2") (pinfunction "2_2") (pintype "passive"))
      (node (ref "R11") (pin "2") (pinfunction "2_2") (pintype "passive"))
      (node (ref "R17") (pin "1") (pinfunction "1_1") (pintype "passive"))
      (node (ref "R18") (pin "1") (pinfunction "1_1") (pintype "passive"))
      (node (ref "R20") (pin "2") (pinfunction "2_2") (pintype "passive"))
      (node (ref "R22") (pin "1") (pinfunction "1_1") (pintype "passive"))
      (node (ref "R23") (pin "1") (pinfunction "1_1") (pintype "passive"))
      (node (ref "R3") (pin "1") (pinfunction "1_1") (pintype "passive"))
      (node (ref "R9") (pin "1") (pinfunction "1_1") (pintype "passive"))
      (node (ref "SWD") (pin "1") (pinfunction "S_1") (pintype "passive"))
      (node (ref "U$3") (pin "5") (pinfunction "VCC_5") (pintype "bidirectional"))
      (node (ref "U1") (pin "1") (pinfunction "VBAT_1") (pintype "power_in"))
      (node (ref "U1") (pin "19") (pinfunction "VDD_4_19") (pintype "power_in"))
      (node (ref "U1") (pin "32") (pinfunction "VDD_1_32") (pintype "power_in"))
      (node (ref "U1") (pin "48") (pinfunction "VDD_2_48") (pintype "power_in"))
      (node (ref "U1") (pin "64") (pinfunction "VDD_3_64") (pintype "power_in"))
    )
    (net (code "74") (name "VDD") (class "Default")
      (node (ref "BAT60JFILM") (pin "C") (pinfunction "C_C") (pintype "passive"))
      (node (ref "IC1") (pin "3") (pinfunction "VIN_3") (pintype "input"))
      (node (ref "NL-652ETTL") (pin "1") (pinfunction "S_1") (pintype "passive"))
    )
    (net (code "75") (name "unconnected-(U$3-GPIO2-Pad8)") (class "Default")
      (node (ref "U$3") (pin "8") (pinfunction "GPIO2_8") (pintype "bidirectional"))
    )
    (net (code "76") (name "unconnected-(U1B-PA11-Pad44)") (class "Default")
      (node (ref "U1") (pin "44") (pinfunction "PA11_44") (pintype "bidirectional"))
    )
    (net (code "77") (name "unconnected-(U1B-PA15-Pad50)") (class "Default")
      (node (ref "U1") (pin "50") (pinfunction "PA15_50") (pintype "bidirectional"))
    )
    (net (code "78") (name "unconnected-(U1E-PB4-Pad56)") (class "Default")
      (node (ref "U1") (pin "56") (pinfunction "PB4_56") (pintype "bidirectional"))
    )
    (net (code "79") (name "unconnected-(U1E-PB5-Pad57)") (class "Default")
      (node (ref "U1") (pin "57") (pinfunction "PB5_57") (pintype "bidirectional"))
    )
    (net (code "80") (name "unconnected-(U1F-PC8-Pad39)") (class "Default")
      (node (ref "U1") (pin "39") (pinfunction "PC8_39") (pintype "bidirectional"))
    )
    (net (code "81") (name "unconnected-(U1F-PC13-Pad2)") (class "Default")
      (node (ref "U1") (pin "2") (pinfunction "PC13_2") (pintype "bidirectional"))
    )
    (net (code "82") (name "unconnected-(U1F-PC14-Pad3)") (class "Default")
      (node (ref "U1") (pin "3") (pinfunction "PC14_3") (pintype "bidirectional"))
    )
    (net (code "83") (name "unconnected-(U1F-PC15-Pad4)") (class "Default")
      (node (ref "U1") (pin "4") (pinfunction "PC15_4") (pintype "bidirectional"))
    )
    (net (code "84") (name "unconnected-(U1G-PC0-Pad8)") (class "Default")
      (node (ref "U1") (pin "8") (pinfunction "PC0_8") (pintype "bidirectional"))
    )
    (net (code "85") (name "unconnected-(U1G-PC3-Pad11)") (class "Default")
      (node (ref "U1") (pin "11") (pinfunction "PC3_11") (pintype "bidirectional"))
    )
    (net (code "86") (name "unconnected-(U1G-PC5-Pad25)") (class "Default")
      (node (ref "U1") (pin "25") (pinfunction "PC5_25") (pintype "bidirectional"))
    )
    (net (code "87") (name "unconnected-(U1H-PD2-Pad54)") (class "Default")
      (node (ref "U1") (pin "54") (pinfunction "PD2_54") (pintype "bidirectional"))
    )
  )
)
